# FMC_Clocks.net
KiCad netlist of a schematic drawn in Altium Designer
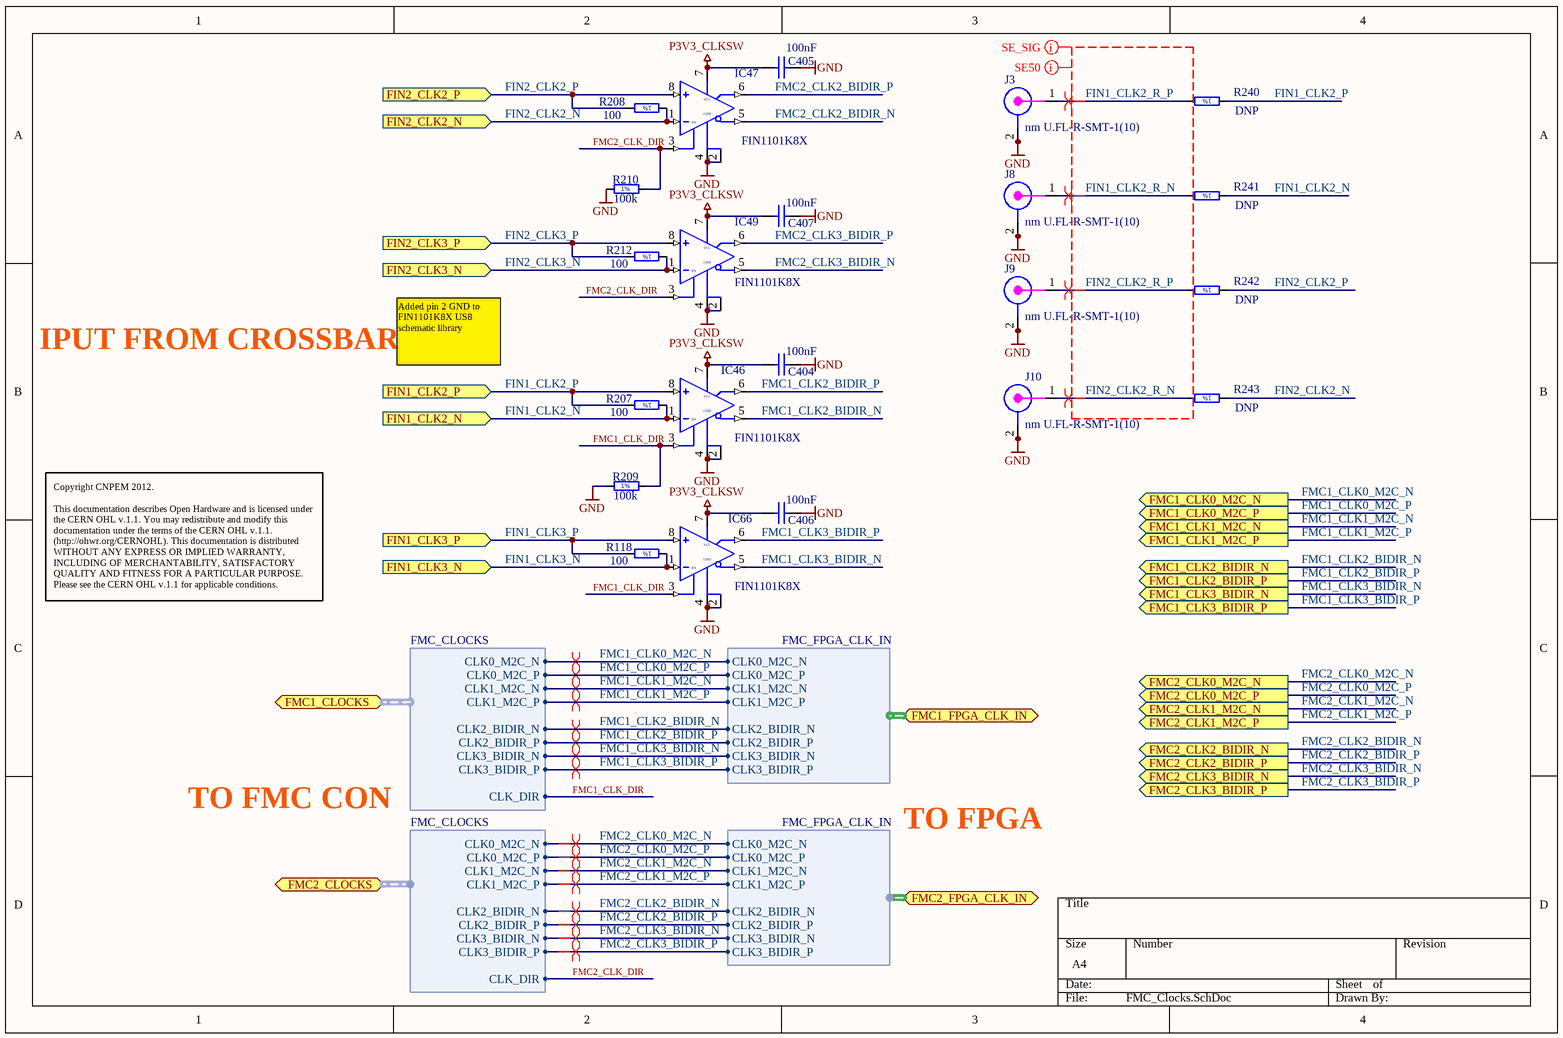
[diagram p0: FMC_Clocks.SchDoc]

(export (version "E")
  (design (tool "Eeschema 10.0.6"))
  (components
    (comp (ref "C404")
      (value "100nF")
      (footprint "CAPC0603X33N")
      (description "Non-polarised capacitor")
      (fields
        (field (name "PART NUMBER") "CC0201_100NF_6.3V_10%_X5R")
        (field (name "VOLTAGE") "6.3V")
        (field (name "AUTHOR") "CERN DEM JLC")
      )
      (libsource (lib "Capacitors") (part "Capacitor - non polarized"))
    )
    (comp (ref "C405")
      (value "100nF")
      (footprint "CAPC0603X33N")
      (description "Non-polarised capacitor")
      (fields
        (field (name "PART NUMBER") "CC0201_100NF_6.3V_10%_X5R")
        (field (name "VOLTAGE") "6.3V")
        (field (name "AUTHOR") "CERN DEM JLC")
      )
      (libsource (lib "Capacitors") (part "Capacitor - non polarized"))
    )
    (comp (ref "C406")
      (value "100nF")
      (footprint "CAPC0603X33N")
      (description "Non-polarised capacitor")
      (fields
        (field (name "PART NUMBER") "CC0201_100NF_6.3V_10%_X5R")
        (field (name "VOLTAGE") "6.3V")
        (field (name "AUTHOR") "CERN DEM JLC")
      )
      (libsource (lib "Capacitors") (part "Capacitor - non polarized"))
    )
    (comp (ref "C407")
      (value "100nF")
      (footprint "CAPC0603X33N")
      (description "Non-polarised capacitor")
      (fields
        (field (name "PART NUMBER") "CC0201_100NF_6.3V_10%_X5R")
        (field (name "VOLTAGE") "6.3V")
        (field (name "AUTHOR") "CERN DEM JLC")
      )
      (libsource (lib "Capacitors") (part "Capacitor - non polarized"))
    )
    (comp (ref "IC46")
      (value "FIN1101K8X")
      (footprint "US8")
      (description "LVDS TO LVDS repeater3.3V")
      (libsource (lib "AMC_FMC_Carrier") (part "IFC_FIN1101K8X"))
    )
    (comp (ref "IC47")
      (value "FIN1101K8X")
      (footprint "US8")
      (description "LVDS TO LVDS repeater3.3V")
      (libsource (lib "AMC_FMC_Carrier") (part "IFC_FIN1101K8X"))
    )
    (comp (ref "IC49")
      (value "FIN1101K8X")
      (footprint "US8")
      (description "LVDS TO LVDS repeater3.3V")
      (libsource (lib "AMC_FMC_Carrier") (part "IFC_FIN1101K8X"))
    )
    (comp (ref "IC66")
      (value "FIN1101K8X")
      (footprint "US8")
      (description "LVDS TO LVDS repeater3.3V")
      (libsource (lib "AMC_FMC_Carrier") (part "IFC_FIN1101K8X"))
    )
    (comp (ref "J3")
      (value "nm U.FL-R-SMT-1(10)")
      (footprint "CON_UFL_HIROSE_RECEPTACLE")
      (description "UFL")
      (libsource (lib "LIBRARY_SCH") (part "CON_UFL_SMD"))
    )
    (comp (ref "J8")
      (value "nm U.FL-R-SMT-1(10)")
      (footprint "CON_UFL_HIROSE_RECEPTACLE")
      (description "UFL")
      (libsource (lib "LIBRARY_SCH") (part "CON_UFL_SMD"))
    )
    (comp (ref "J9")
      (value "nm U.FL-R-SMT-1(10)")
      (footprint "CON_UFL_HIROSE_RECEPTACLE")
      (description "UFL")
      (libsource (lib "LIBRARY_SCH") (part "CON_UFL_SMD"))
    )
    (comp (ref "J10")
      (value "nm U.FL-R-SMT-1(10)")
      (footprint "CON_UFL_HIROSE_RECEPTACLE")
      (description "UFL")
      (libsource (lib "LIBRARY_SCH") (part "CON_UFL_SMD"))
    )
    (comp (ref "R118")
      (value "100")
      (footprint "RESC1005X40N")
      (description "Resistor - 1%")
      (fields
        (field (name "PART NUMBER") "R0402_100R_1%_0.0625W_100PPM")
        (field (name "POWER") "0.0625W")
        (field (name "AUTHOR") "CERN DEM JLC")
      )
      (libsource (lib "Resistors") (part "Resistor - 1%"))
    )
    (comp (ref "R207")
      (value "100")
      (footprint "RESC1005X40N")
      (description "Resistor - 1%")
      (fields
        (field (name "PART NUMBER") "R0402_100R_1%_0.0625W_100PPM")
        (field (name "POWER") "0.0625W")
        (field (name "AUTHOR") "CERN DEM JLC")
      )
      (libsource (lib "Resistors") (part "Resistor - 1%"))
    )
    (comp (ref "R208")
      (value "100")
      (footprint "RESC1005X40N")
      (description "Resistor - 1%")
      (fields
        (field (name "PART NUMBER") "R0402_100R_1%_0.0625W_100PPM")
        (field (name "POWER") "0.0625W")
        (field (name "AUTHOR") "CERN DEM JLC")
      )
      (libsource (lib "Resistors") (part "Resistor - 1%"))
    )
    (comp (ref "R209")
      (value "100k")
      (footprint "RESC1005X40N")
      (description "Resistor - 1%")
      (fields
        (field (name "PART NUMBER") "R0402_100K_1%_0.0625W_100PPM")
        (field (name "POWER") "0.0625W")
        (field (name "AUTHOR") "CERN DEM JLC")
      )
      (libsource (lib "Resistors") (part "Resistor - 1%"))
    )
    (comp (ref "R210")
      (value "100k")
      (footprint "RESC1005X40N")
      (description "Resistor - 1%")
      (fields
        (field (name "PART NUMBER") "R0402_100K_1%_0.0625W_100PPM")
        (field (name "POWER") "0.0625W")
        (field (name "AUTHOR") "CERN DEM JLC")
      )
      (libsource (lib "Resistors") (part "Resistor - 1%"))
    )
    (comp (ref "R212")
      (value "100")
      (footprint "RESC1005X40N")
      (description "Resistor - 1%")
      (fields
        (field (name "PART NUMBER") "R0402_100R_1%_0.0625W_100PPM")
        (field (name "POWER") "0.0625W")
        (field (name "AUTHOR") "CERN DEM JLC")
      )
      (libsource (lib "Resistors") (part "Resistor - 1%"))
    )
    (comp (ref "R240")
      (value "DNP")
      (footprint "RESC1005X40N")
      (description "Resistor - 1%")
      (fields
        (field (name "PART NUMBER") "R0402_0R_JUMPER")
        (field (name "MANUFACTURER") "GENERIC")
        (field (name "AUTHOR") "CERN DEM JLC")
      )
      (libsource (lib "Resistors") (part "Resistor - 1%"))
    )
    (comp (ref "R241")
      (value "DNP")
      (footprint "RESC1005X40N")
      (description "Resistor - 1%")
      (fields
        (field (name "PART NUMBER") "R0402_0R_JUMPER")
        (field (name "MANUFACTURER") "GENERIC")
        (field (name "AUTHOR") "CERN DEM JLC")
      )
      (libsource (lib "Resistors") (part "Resistor - 1%"))
    )
    (comp (ref "R242")
      (value "DNP")
      (footprint "RESC1005X40N")
      (description "Resistor - 1%")
      (fields
        (field (name "PART NUMBER") "R0402_0R_JUMPER")
        (field (name "MANUFACTURER") "GENERIC")
        (field (name "AUTHOR") "CERN DEM JLC")
      )
      (libsource (lib "Resistors") (part "Resistor - 1%"))
    )
    (comp (ref "R243")
      (value "DNP")
      (footprint "RESC1005X40N")
      (description "Resistor - 1%")
      (fields
        (field (name "PART NUMBER") "R0402_0R_JUMPER")
        (field (name "MANUFACTURER") "GENERIC")
        (field (name "AUTHOR") "CERN DEM JLC")
      )
      (libsource (lib "Resistors") (part "Resistor - 1%"))
    )
  )
  (nets
    (net (code "3") (name "/FIN1_CLK2_N") (class "Default")
      (node (ref "IC46") (pin "1") (pinfunction "IN_1") (pintype "input"))
      (node (ref "R207") (pin "1") (pinfunction "1_1") (pintype "passive"))
      (node (ref "R241") (pin "1") (pinfunction "1_1") (pintype "passive"))
    )
    (net (code "4") (name "/FIN1_CLK2_P") (class "Default")
      (node (ref "IC46") (pin "8") (pinfunction "IN_8") (pintype "input"))
      (node (ref "R207") (pin "2") (pinfunction "2_2") (pintype "passive"))
      (node (ref "R240") (pin "1") (pinfunction "1_1") (pintype "passive"))
    )
    (net (code "5") (name "/FIN1_CLK2_R_N") (class "Default")
      (node (ref "J8") (pin "1") (pintype "passive"))
      (node (ref "R241") (pin "2") (pinfunction "2_2") (pintype "passive"))
    )
    (net (code "6") (name "/FIN1_CLK2_R_P") (class "Default")
      (node (ref "J3") (pin "1") (pintype "passive"))
      (node (ref "R240") (pin "2") (pinfunction "2_2") (pintype "passive"))
    )
    (net (code "7") (name "/FIN1_CLK3_N") (class "Default")
      (node (ref "IC66") (pin "1") (pinfunction "IN_1") (pintype "input"))
      (node (ref "R118") (pin "1") (pinfunction "1_1") (pintype "passive"))
    )
    (net (code "8") (name "/FIN1_CLK3_P") (class "Default")
      (node (ref "IC66") (pin "8") (pinfunction "IN_8") (pintype "input"))
      (node (ref "R118") (pin "2") (pinfunction "2_2") (pintype "passive"))
    )
    (net (code "9") (name "/FIN2_CLK2_N") (class "Default")
      (node (ref "IC47") (pin "1") (pinfunction "IN_1") (pintype "input"))
      (node (ref "R208") (pin "1") (pinfunction "1_1") (pintype "passive"))
      (node (ref "R243") (pin "1") (pinfunction "1_1") (pintype "passive"))
    )
    (net (code "10") (name "/FIN2_CLK2_P") (class "Default")
      (node (ref "IC47") (pin "8") (pinfunction "IN_8") (pintype "input"))
      (node (ref "R208") (pin "2") (pinfunction "2_2") (pintype "passive"))
      (node (ref "R242") (pin "1") (pinfunction "1_1") (pintype "passive"))
    )
    (net (code "11") (name "/FIN2_CLK2_R_N") (class "Default")
      (node (ref "J10") (pin "1") (pintype "passive"))
      (node (ref "R243") (pin "2") (pinfunction "2_2") (pintype "passive"))
    )
    (net (code "12") (name "/FIN2_CLK2_R_P") (class "Default")
      (node (ref "J9") (pin "1") (pintype "passive"))
      (node (ref "R242") (pin "2") (pinfunction "2_2") (pintype "passive"))
    )
    (net (code "13") (name "/FIN2_CLK3_N") (class "Default")
      (node (ref "IC49") (pin "1") (pinfunction "IN_1") (pintype "input"))
      (node (ref "R212") (pin "1") (pinfunction "1_1") (pintype "passive"))
    )
    (net (code "14") (name "/FIN2_CLK3_P") (class "Default")
      (node (ref "IC49") (pin "8") (pinfunction "IN_8") (pintype "input"))
      (node (ref "R212") (pin "2") (pinfunction "2_2") (pintype "passive"))
    )
    (net (code "19") (name "/FMC1_CLK2_BIDIR_N") (class "Default")
      (node (ref "IC46") (pin "5") (pinfunction "~{Q}_5") (pintype "output"))
    )
    (net (code "20") (name "/FMC1_CLK2_BIDIR_P") (class "Default")
      (node (ref "IC46") (pin "6") (pinfunction "Q_6") (pintype "output"))
    )
    (net (code "21") (name "/FMC1_CLK3_BIDIR_N") (class "Default")
      (node (ref "IC66") (pin "5") (pinfunction "~{Q}_5") (pintype "output"))
    )
    (net (code "22") (name "/FMC1_CLK3_BIDIR_P") (class "Default")
      (node (ref "IC66") (pin "6") (pinfunction "Q_6") (pintype "output"))
    )
    (net (code "23") (name "/FMC1_CLK_DIR") (class "Default")
      (node (ref "IC46") (pin "3") (pinfunction "EN_3") (pintype "input"))
      (node (ref "IC66") (pin "3") (pinfunction "EN_3") (pintype "input"))
      (node (ref "R209") (pin "2") (pinfunction "2_2") (pintype "passive"))
    )
    (net (code "28") (name "/FMC2_CLK2_BIDIR_N") (class "Default")
      (node (ref "IC47") (pin "5") (pinfunction "~{Q}_5") (pintype "output"))
    )
    (net (code "29") (name "/FMC2_CLK2_BIDIR_P") (class "Default")
      (node (ref "IC47") (pin "6") (pinfunction "Q_6") (pintype "output"))
    )
    (net (code "30") (name "/FMC2_CLK3_BIDIR_N") (class "Default")
      (node (ref "IC49") (pin "5") (pinfunction "~{Q}_5") (pintype "output"))
    )
    (net (code "31") (name "/FMC2_CLK3_BIDIR_P") (class "Default")
      (node (ref "IC49") (pin "6") (pinfunction "Q_6") (pintype "output"))
    )
    (net (code "32") (name "/FMC2_CLK_DIR") (class "Default")
      (node (ref "IC47") (pin "3") (pinfunction "EN_3") (pintype "input"))
      (node (ref "IC49") (pin "3") (pinfunction "EN_3") (pintype "input"))
      (node (ref "R210") (pin "2") (pinfunction "2_2") (pintype "passive"))
    )
    (net (code "35") (name "GND") (class "Default")
      (node (ref "C404") (pin "2") (pinfunction "2_2") (pintype "passive"))
      (node (ref "C405") (pin "2") (pinfunction "2_2") (pintype "passive"))
      (node (ref "C406") (pin "2") (pinfunction "2_2") (pintype "passive"))
      (node (ref "C407") (pin "2") (pinfunction "2_2") (pintype "passive"))
      (node (ref "IC46") (pin "2") (pinfunction "GND_2") (pintype "power_in"))
      (node (ref "IC46") (pin "4") (pinfunction "GND_4") (pintype "power_in"))
      (node (ref "IC47") (pin "2") (pinfunction "GND_2") (pintype "power_in"))
      (node (ref "IC47") (pin "4") (pinfunction "GND_4") (pintype "power_in"))
      (node (ref "IC49") (pin "2") (pinfunction "GND_2") (pintype "power_in"))
      (node (ref "IC49") (pin "4") (pinfunction "GND_4") (pintype "power_in"))
      (node (ref "IC66") (pin "2") (pinfunction "GND_2") (pintype "power_in"))
      (node (ref "IC66") (pin "4") (pinfunction "GND_4") (pintype "power_in"))
      (node (ref "J10") (pin "2") (pintype "passive"))
      (node (ref "J10") (pin "2a") (pinfunction "GND_2a") (pintype "passive"))
      (node (ref "J3") (pin "2") (pintype "passive"))
      (node (ref "J3") (pin "2a") (pinfunction "GND_2a") (pintype "passive"))
      (node (ref "J8") (pin "2") (pintype "passive"))
      (node (ref "J8") (pin "2a") (pinfunction "GND_2a") (pintype "passive"))
      (node (ref "J9") (pin "2") (pintype "passive"))
      (node (ref "J9") (pin "2a") (pinfunction "GND_2a") (pintype "passive"))
      (node (ref "R209") (pin "1") (pinfunction "1_1") (pintype "passive"))
      (node (ref "R210") (pin "1") (pinfunction "1_1") (pintype "passive"))
    )
    (net (code "36") (name "P3V3_CLKSW") (class "Default")
      (node (ref "C404") (pin "1") (pinfunction "1_1") (pintype "passive"))
      (node (ref "C405") (pin "1") (pinfunction "1_1") (pintype "passive"))
      (node (ref "C406") (pin "1") (pinfunction "1_1") (pintype "passive"))
      (node (ref "C407") (pin "1") (pinfunction "1_1") (pintype "passive"))
      (node (ref "IC46") (pin "7") (pinfunction "VCC_7") (pintype "power_in"))
      (node (ref "IC47") (pin "7") (pinfunction "VCC_7") (pintype "power_in"))
      (node (ref "IC49") (pin "7") (pinfunction "VCC_7") (pintype "power_in"))
      (node (ref "IC66") (pin "7") (pinfunction "VCC_7") (pintype "power_in"))
    )
  )
)
